# QUTMS-TSAL-S01.net
KiCad netlist of a schematic drawn in Altium Designer
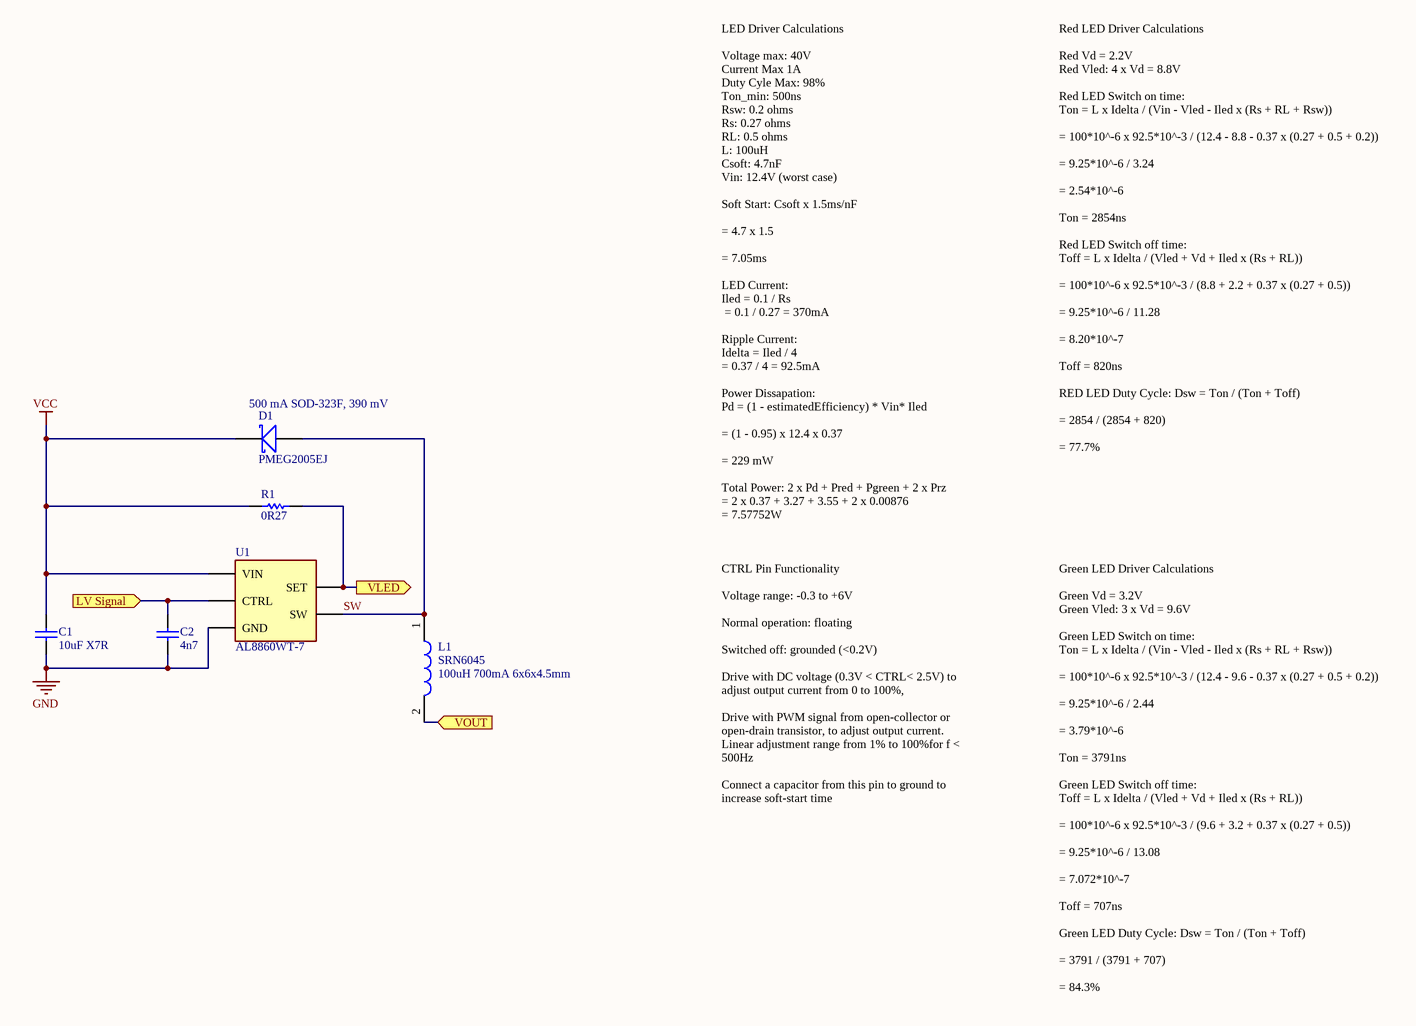
[diagram p0: QUTMS-TSAL-S01.SchDoc]

(export (version "E")
  (design (tool "Eeschema 10.0.6"))
  (components
    (comp (ref "C1")
      (value "10uF X7R")
      (footprint "Cap_Ceramic_0603")
      (description "Capacitor, Ceramic, SMD, 10uF, 50V, 5%, X7R, 0603")
      (libsource (lib "StandardCapacitors") (part "10uF 50V 5% X7R 0603"))
    )
    (comp (ref "C2")
      (value "4n7")
      (footprint "Cap_Ceramic_0603")
      (description "Capacitor, Ceramic, SMD, 4n7, 25V, 5%, X7R, 0603")
      (libsource (lib "StandardCapacitors") (part "4n7 25V 5% X7R 0603"))
    )
    (comp (ref "D1")
      (value "PMEG2005EJ")
      (footprint "SOD-323F")
      (description "PMEG2005EJ,115 -  Schottky Rectifier, 20 V, 500 mA, Single, SOD-323F, 2 Pins, 390 mV")
      (libsource (lib "QUTMS_DiodeLibrary") (part "PMEG2005EJ"))
    )
    (comp (ref "L1")
      (value "SRN6045")
      (footprint "Bourns Inductor 6x6x4.5mm")
      (description "Power Inductor (SMD), 100 µH, 700 mA, Semishielded, 800 mA")
      (libsource (lib "QUTMS_InductorLibrary") (part "SRN6045"))
    )
    (comp (ref "R1")
      (value "0R27")
      (footprint "Res_ThinFilm_0603")
      (libsource (lib "StandardResistors") (part "0R27 1% 0603"))
    )
    (comp (ref "U1")
      (value "AL8860WT-7")
      (footprint "TSOT-25")
      (libsource (lib "QUTMS_PowerSupplyLibrary") (part "AL8860WT-7"))
    )
  )
  (nets
    (net (code "1") (name "/LV Signal") (class "Default")
      (node (ref "C2") (pin "2") (pinfunction "2_2") (pintype "passive"))
      (node (ref "U1") (pin "3") (pinfunction "CTRL_3") (pintype "power_in"))
    )
    (net (code "2") (name "/SW") (class "Default")
      (node (ref "D1") (pin "A") (pinfunction "Anode_A") (pintype "passive"))
      (node (ref "L1") (pin "1") (pinfunction "1_1") (pintype "passive"))
      (node (ref "U1") (pin "1") (pinfunction "SW_1") (pintype "power_in"))
    )
    (net (code "3") (name "/VLED") (class "Default")
      (node (ref "R1") (pin "2") (pinfunction "2_2") (pintype "passive"))
      (node (ref "U1") (pin "4") (pinfunction "SET_4") (pintype "power_in"))
    )
    (net (code "4") (name "/VOUT") (class "Default")
      (node (ref "L1") (pin "2") (pinfunction "2_2") (pintype "passive"))
    )
    (net (code "5") (name "GND") (class "Default")
      (node (ref "C1") (pin "1") (pinfunction "1_1") (pintype "passive"))
      (node (ref "C2") (pin "1") (pinfunction "1_1") (pintype "passive"))
      (node (ref "U1") (pin "2") (pinfunction "GND_2") (pintype "power_in"))
    )
    (net (code "6") (name "VCC") (class "Default")
      (node (ref "C1") (pin "2") (pinfunction "2_2") (pintype "passive"))
      (node (ref "D1") (pin "K") (pinfunction "Cathode_K") (pintype "passive"))
      (node (ref "R1") (pin "1") (pinfunction "1_1") (pintype "passive"))
      (node (ref "U1") (pin "5") (pinfunction "VIN_5") (pintype "power_in"))
    )
  )
)
